# BDAN_PWR.net
KiCad netlist of a schematic drawn in Altium Designer
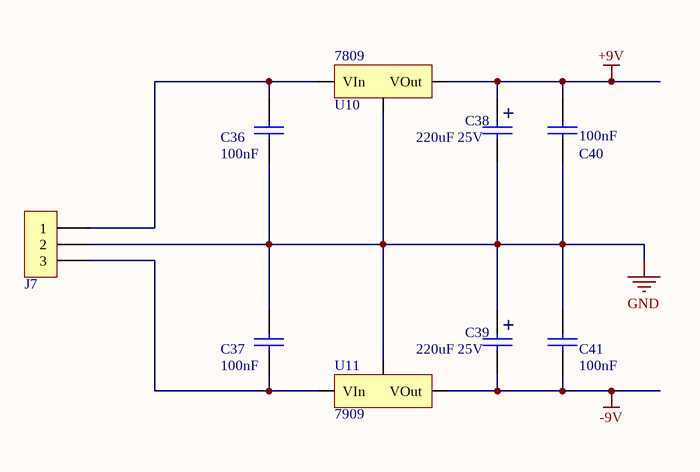
[diagram p0: BDAN_PWR.SchDoc]

(export (version "E")
  (design (tool "Eeschema 10.0.6"))
  (components
    (comp (ref "C36")
      (value "100nF")
      (footprint "0805")
      (description "CAP0805 100nF X7R")
      (fields (field (name "PART NUMBER") "CAP0805_100nF_X7R"))
      (libsource (lib "gl_LIB") (part "CAP"))
    )
    (comp (ref "C37")
      (value "100nF")
      (footprint "0805")
      (description "CAP0805 100nF X7R")
      (fields (field (name "PART NUMBER") "CAP0805_100nF_X7R"))
      (libsource (lib "gl_LIB") (part "CAP"))
    )
    (comp (ref "C38")
      (value "220uF 25V")
      (footprint "CAP300RP")
      (description "CAP ELECT 220uF 25V")
      (fields (field (name "PART NUMBER") "CAP_ELECT_220uF_25V") (field (name "MANUFACTURER") "Nichicon"))
      (libsource (lib "gl_LIB") (part "CAPPOL"))
    )
    (comp (ref "C39")
      (value "220uF 25V")
      (footprint "CAP300RP")
      (description "CAP ELECT 220uF 25V")
      (fields (field (name "PART NUMBER") "CAP_ELECT_220uF_25V") (field (name "MANUFACTURER") "Nichicon"))
      (libsource (lib "gl_LIB") (part "CAPPOL"))
    )
    (comp (ref "C40")
      (value "100nF")
      (footprint "0805")
      (description "CAP0805 100nF X7R")
      (fields (field (name "PART NUMBER") "CAP0805_100nF_X7R"))
      (libsource (lib "gl_LIB") (part "CAP"))
    )
    (comp (ref "C41")
      (value "100nF")
      (footprint "0805")
      (description "CAP0805 100nF X7R")
      (fields (field (name "PART NUMBER") "CAP0805_100nF_X7R"))
      (libsource (lib "gl_LIB") (part "CAP"))
    )
    (comp (ref "J7")
      (value "1984620")
      (footprint "BORNERA3_3.5MM")
      (description "TERM BLK 3P SIDE ENT 3.5MM PCB")
      (fields
        (field (name "PART NUMBER") "BORNERA_3_3.5MM_TORNILLO")
        (field (name "MANUFACTURER") "Phoenix Contact")
      )
      (libsource (lib "gl_LIB") (part "CON3"))
    )
    (comp (ref "U10")
      (value "7809")
      (footprint "TO220-V")
      (description "IC REG LDO 9V 1.5A TO220")
      (libsource (lib "gl_LIB") (part "78XX"))
    )
    (comp (ref "U11")
      (value "7909")
      (footprint "TO220-V")
      (description "IC REG LDO -9V 1.5A TO220")
      (libsource (lib "gl_LIB") (part "79XX"))
    )
  )
  (nets
    (net (code "1") (name "+9V") (class "Default")
      (node (ref "C38") (pin "1") (pinfunction "1_1") (pintype "passive"))
      (node (ref "C40") (pin "1") (pinfunction "1_1") (pintype "passive"))
      (node (ref "U10") (pin "3") (pinfunction "VOut_3") (pintype "passive"))
    )
    (net (code "2") (name "-9V") (class "Default")
      (node (ref "C39") (pin "2") (pinfunction "2_2") (pintype "passive"))
      (node (ref "C41") (pin "2") (pinfunction "2_2") (pintype "passive"))
      (node (ref "U11") (pin "3") (pinfunction "VOut_3") (pintype "passive"))
    )
    (net (code "3") (name "GND") (class "Default")
      (node (ref "C36") (pin "2") (pinfunction "2_2") (pintype "passive"))
      (node (ref "C37") (pin "1") (pinfunction "1_1") (pintype "passive"))
      (node (ref "C38") (pin "2") (pinfunction "2_2") (pintype "passive"))
      (node (ref "C39") (pin "1") (pinfunction "1_1") (pintype "passive"))
      (node (ref "C40") (pin "2") (pinfunction "2_2") (pintype "passive"))
      (node (ref "C41") (pin "1") (pinfunction "1_1") (pintype "passive"))
      (node (ref "J7") (pin "2") (pinfunction "2_2") (pintype "passive"))
      (node (ref "U10") (pin "2") (pinfunction "GND_2") (pintype "passive"))
      (node (ref "U11") (pin "1") (pinfunction "GND_1") (pintype "passive"))
    )
    (net (code "4") (name "Net-(U10-VIn)") (class "Default")
      (node (ref "C36") (pin "1") (pinfunction "1_1") (pintype "passive"))
      (node (ref "J7") (pin "1") (pinfunction "1_1") (pintype "passive"))
      (node (ref "U10") (pin "1") (pinfunction "VIn_1") (pintype "passive"))
    )
    (net (code "5") (name "Net-(U11-VIn)") (class "Default")
      (node (ref "C37") (pin "2") (pinfunction "2_2") (pintype "passive"))
      (node (ref "J7") (pin "3") (pinfunction "3_3") (pintype "passive"))
      (node (ref "U11") (pin "2") (pinfunction "VIn_2") (pintype "passive"))
    )
  )
)
